# easyeda.net
KiCad netlist of a schematic drawn in EasyEDA
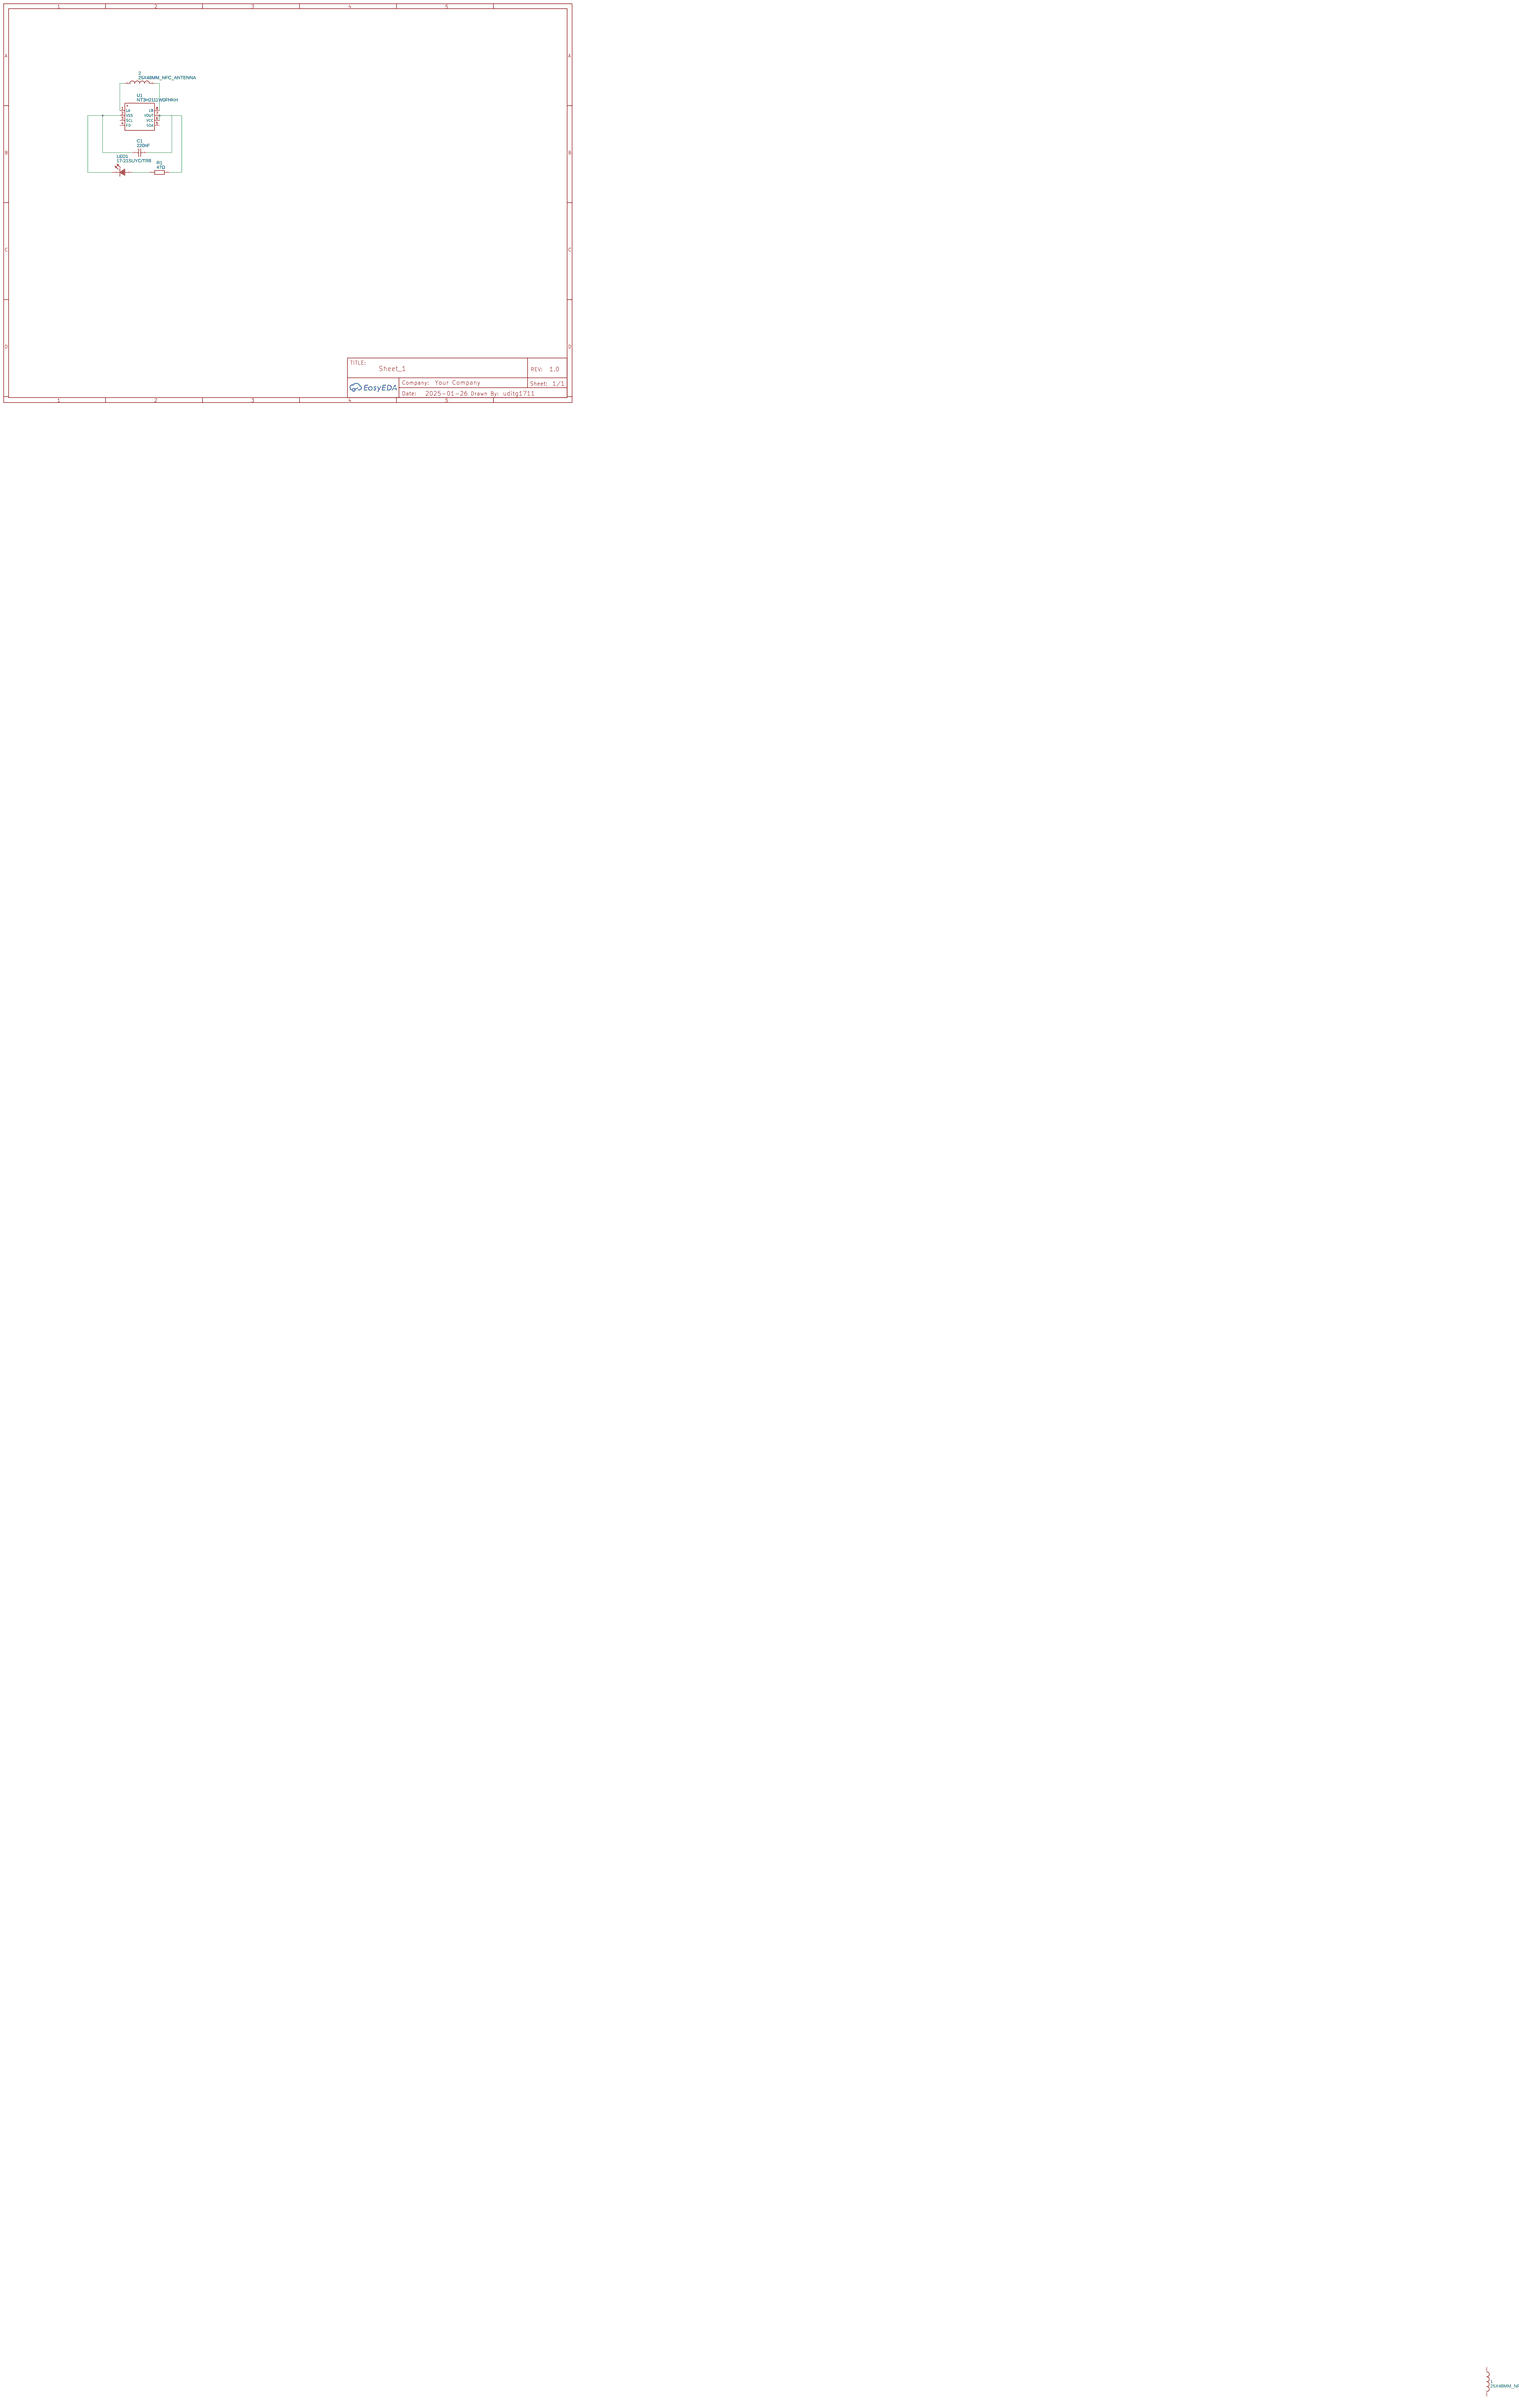
[diagram p0: schematic sheet]

(export (version "E")
  (design (tool "Eeschema 10.0.6"))
  (components
    (comp (ref "1") (value "25X48MM_NFC_ANTENNA") (libsource (lib "") (part "25X48MM_NFC_ANTENNA_1")))
    (comp (ref "2") (value "25X48MM_NFC_ANTENNA") (libsource (lib "") (part "25X48MM_NFC_ANTENNA")))
    (comp (ref "C1")
      (value "220nF")
      (fields
        (field (name "Manufacturer Part") "CL10B224KA8NNNC")
        (field (name "Manufacturer") "SAMSUNG(三星)")
      )
      (libsource (lib "") (part "CL10B224KA8NNNC"))
    )
    (comp (ref "LED1")
      (value "17-21SUYC/TR8")
      (fields (field (name "Manufacturer Part") "KT-0805黄灯") (field (name "Manufacturer") "KENTO"))
      (libsource (lib "") (part "17-21SUYC/TR8"))
    )
    (comp (ref "R1")
      (value "47Ω")
      (fields
        (field (name "Manufacturer Part") "0603WAF470JT5E")
        (field (name "Manufacturer") "UNI-ROYAL(厚声)")
      )
      (libsource (lib "") (part "0603WAF470JT5E"))
    )
    (comp (ref "U1")
      (value "NT3H2111W0FHKH")
      (fields (field (name "Manufacturer") "NXP(恩智浦)"))
      (libsource (lib "") (part "NT3H2111W0FHKH"))
    )
  )
  (nets
    (net (code "1") (name "Net-(LED1-+)") (class "Default")
      (node (ref "LED1") (pin "1") (pinfunction "+_1") (pintype "unspecified"))
      (node (ref "R1") (pin "1") (pinfunction "1_1") (pintype "input"))
    )
    (net (code "2") (name "Net-(LED1--)") (class "Default")
      (node (ref "C1") (pin "1") (pinfunction "1_1") (pintype "input"))
      (node (ref "LED1") (pin "2") (pinfunction "-_2") (pintype "unspecified"))
      (node (ref "U1") (pin "2") (pinfunction "VSS_2") (pintype "unspecified"))
    )
    (net (code "3") (name "Net-(U1-LA)") (class "Default")
      (node (ref "2") (pin "P$1") (pinfunction "P$1_P$1") (pintype "bidirectional"))
      (node (ref "U1") (pin "1") (pinfunction "LA_1") (pintype "unspecified"))
    )
    (net (code "4") (name "Net-(U1-LB)") (class "Default")
      (node (ref "2") (pin "P$2") (pinfunction "P$2_P$2") (pintype "bidirectional"))
      (node (ref "U1") (pin "8") (pinfunction "LB_8") (pintype "unspecified"))
    )
    (net (code "5") (name "Net-(U1-VCC)") (class "Default")
      (node (ref "C1") (pin "2") (pinfunction "2_2") (pintype "input"))
      (node (ref "R1") (pin "2") (pinfunction "2_2") (pintype "input"))
      (node (ref "U1") (pin "6") (pinfunction "VCC_6") (pintype "unspecified"))
      (node (ref "U1") (pin "7") (pinfunction "VOUT_7") (pintype "unspecified"))
    )
    (net (code "6") (name "unconnected-(1-PadP$1)") (class "Default")
      (node (ref "1") (pin "P$1") (pinfunction "P$1_P$1") (pintype "bidirectional"))
    )
    (net (code "7") (name "unconnected-(1-PadP$2)") (class "Default")
      (node (ref "1") (pin "P$2") (pinfunction "P$2_P$2") (pintype "bidirectional"))
    )
    (net (code "8") (name "unconnected-(U1-FD-Pad4)") (class "Default")
      (node (ref "U1") (pin "4") (pinfunction "FD_4") (pintype "unspecified"))
    )
    (net (code "9") (name "unconnected-(U1-SCL-Pad3)") (class "Default")
      (node (ref "U1") (pin "3") (pinfunction "SCL_3") (pintype "unspecified"))
    )
    (net (code "10") (name "unconnected-(U1-SDA-Pad5)") (class "Default")
      (node (ref "U1") (pin "5") (pinfunction "SDA_5") (pintype "unspecified"))
    )
  )
)
